# Comparator.net
KiCad netlist of a schematic drawn in Altium Designer
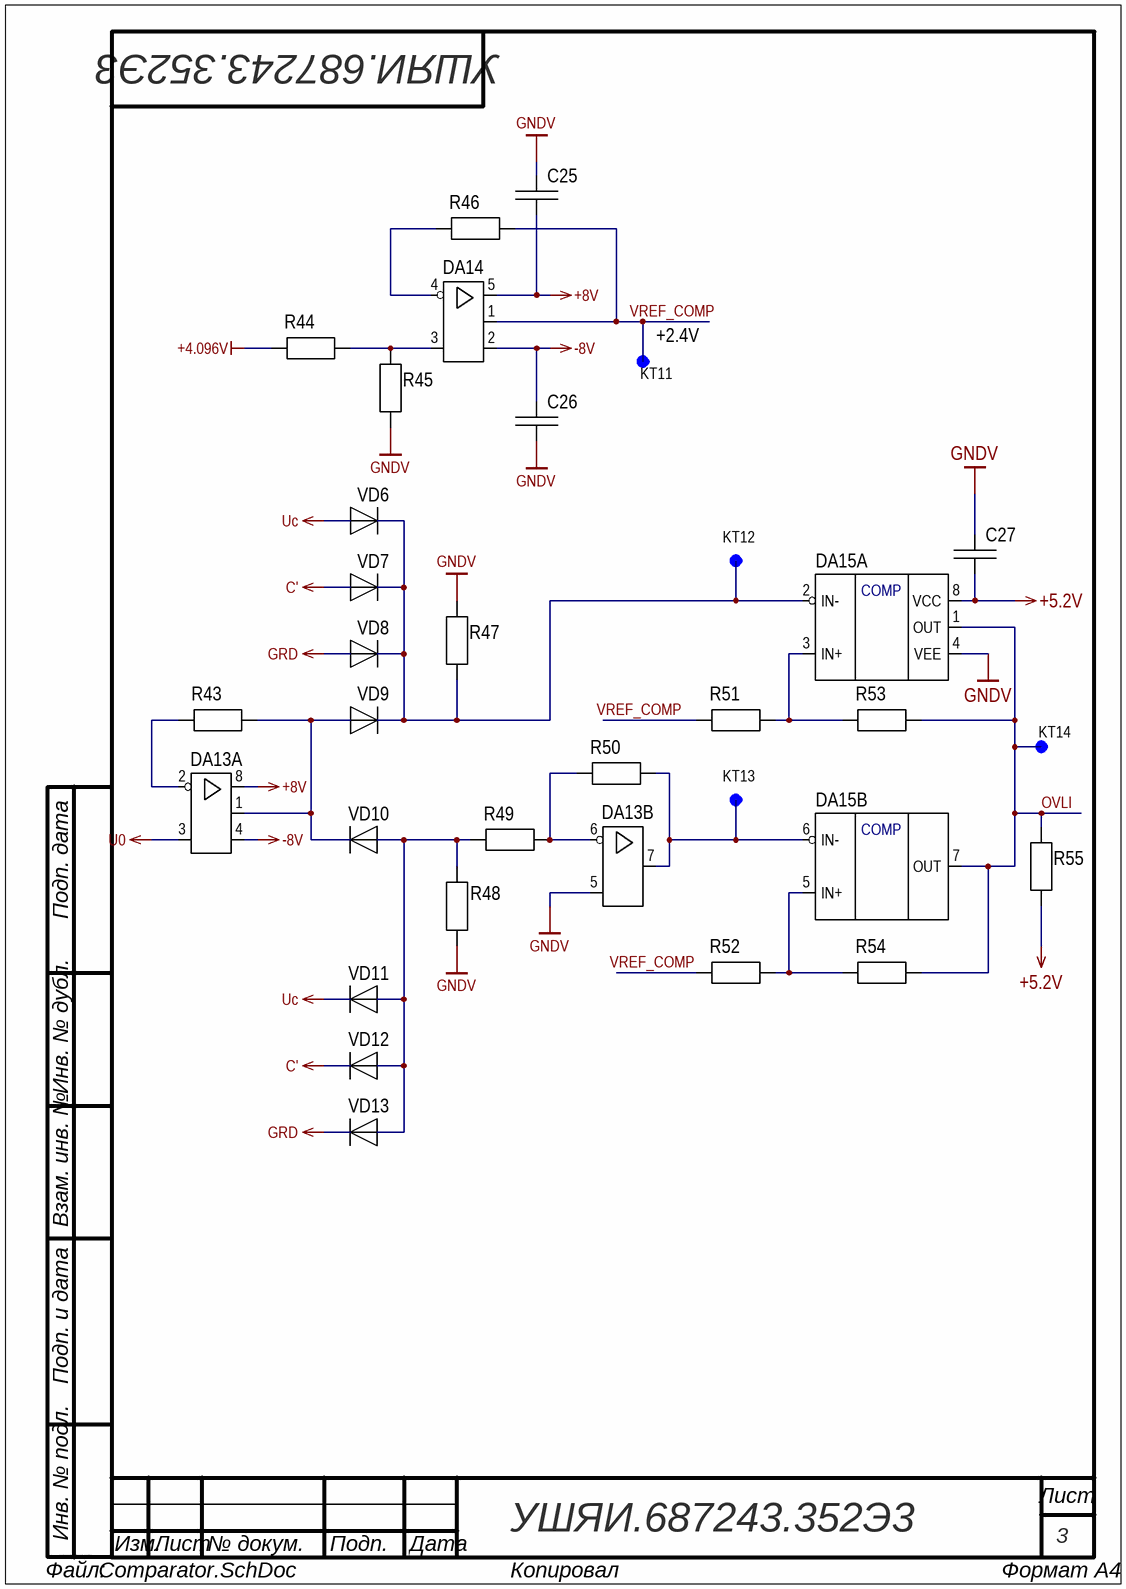
[diagram p0: Comparator.SchDoc]

(export (version "E")
  (design (tool "Eeschema 10.0.6"))
  (components
    (comp (ref "C25")
      (value "1206-X7R-50 B-0,1 мкФ+-10%")
      (footprint "standard-case:CAP: 1206")
      (libsource (lib "МНИПИ_Конденсаторы") (part "1206-X7R-50 B-0,1 мкФ+-10%"))
    )
    (comp (ref "C26")
      (value "1206-X7R-50 B-0,1 мкФ+-10%")
      (footprint "standard-case:CAP: 1206")
      (libsource (lib "МНИПИ_Конденсаторы") (part "1206-X7R-50 B-0,1 мкФ+-10%"))
    )
    (comp (ref "C27")
      (value "1206-X7R-50 B-0,1 мкФ+-10%")
      (footprint "standard-case:CAP: 1206")
      (libsource (lib "МНИПИ_Конденсаторы") (part "1206-X7R-50 B-0,1 мкФ+-10%"))
    )
    (comp (ref "DA13")
      (value "TLV9152IDR")
      (footprint "8-SOIC")
      (libsource (lib "МНИПИ_Микросхемы") (part "TLV9152IDR"))
    )
    (comp (ref "DA14")
      (value "TLV9151IDR")
      (footprint "SOT-23-5")
      (libsource (lib "МНИПИ_Микросхемы") (part "TLV9151IDR"))
    )
    (comp (ref "DA15")
      (value "TLV1842")
      (footprint "8-VSSOP")
      (description "40V, High-Speed Comparators")
      (libsource (lib "МНИПИ_Микросхемы") (part "TLV1842"))
    )
    (comp (ref "KT11") (value "OTV10") (footprint "OTV10") (libsource (lib "МНИПИ_Остальное") (part "OTV10")))
    (comp (ref "KT12") (value "OTV10") (footprint "OTV10") (libsource (lib "МНИПИ_Остальное") (part "OTV10")))
    (comp (ref "KT13") (value "OTV10") (footprint "OTV10") (libsource (lib "МНИПИ_Остальное") (part "OTV10")))
    (comp (ref "KT14") (value "OTV10") (footprint "OTV10") (libsource (lib "МНИПИ_Остальное") (part "OTV10")))
    (comp (ref "R43")
      (value "1206-470 Ом+-5%")
      (footprint "МНИПИ_Резисторы:1206")
      (libsource (lib "МНИПИ_Резисторы") (part "1206-470 Ом+-5%"))
    )
    (comp (ref "R44")
      (value "1206-7,15 кОм+-1%")
      (footprint "МНИПИ_Резисторы:1206")
      (libsource (lib "МНИПИ_Резисторы") (part "1206-7,15 кОм+-1%"))
    )
    (comp (ref "R45")
      (value "1206-10 кОм+-0,5%")
      (footprint "МНИПИ_Резисторы:1206")
      (libsource (lib "МНИПИ_Резисторы") (part "1206-10 кОм+-0,5%"))
    )
    (comp (ref "R46")
      (value "1206-470 Ом+-5%")
      (footprint "МНИПИ_Резисторы:1206")
      (libsource (lib "МНИПИ_Резисторы") (part "1206-470 Ом+-5%"))
    )
    (comp (ref "R47")
      (value "1206-2,4 кОм+-5%")
      (footprint "МНИПИ_Резисторы:1206")
      (libsource (lib "МНИПИ_Резисторы") (part "1206-2,4 кОм+-5%"))
    )
    (comp (ref "R48")
      (value "1206-2,4 кОм+-5%")
      (footprint "МНИПИ_Резисторы:1206")
      (libsource (lib "МНИПИ_Резисторы") (part "1206-2,4 кОм+-5%"))
    )
    (comp (ref "R49")
      (value "0805-1 кОм+-0,1%")
      (footprint "МНИПИ_Резисторы:0805")
      (libsource (lib "МНИПИ_Резисторы") (part "0805-1 кОм+-0,1%"))
    )
    (comp (ref "R50")
      (value "0805-1 кОм+-0,1%")
      (footprint "МНИПИ_Резисторы:0805")
      (libsource (lib "МНИПИ_Резисторы") (part "0805-1 кОм+-0,1%"))
    )
    (comp (ref "R51")
      (value "0805-1 кОм+-0,1%")
      (footprint "МНИПИ_Резисторы:0805")
      (libsource (lib "МНИПИ_Резисторы") (part "0805-1 кОм+-0,1%"))
    )
    (comp (ref "R52")
      (value "0805-1 кОм+-0,1%")
      (footprint "МНИПИ_Резисторы:0805")
      (libsource (lib "МНИПИ_Резисторы") (part "0805-1 кОм+-0,1%"))
    )
    (comp (ref "R53")
      (value "1206-510 кОм+-1%")
      (footprint "МНИПИ_Резисторы:1206")
      (libsource (lib "МНИПИ_Резисторы") (part "1206-510 кОм+-1%"))
    )
    (comp (ref "R54")
      (value "1206-510 кОм+-1%")
      (footprint "МНИПИ_Резисторы:1206")
      (libsource (lib "МНИПИ_Резисторы") (part "1206-510 кОм+-1%"))
    )
    (comp (ref "R55")
      (value "1206-4,7 кОм+-5%")
      (footprint "МНИПИ_Резисторы:1206")
      (libsource (lib "МНИПИ_Резисторы") (part "1206-4,7 кОм+-5%"))
    )
    (comp (ref "VD6")
      (value "1N4148WS")
      (footprint "SOD-323F")
      (description "Small Signal Fast Switching Diod")
      (libsource (lib "МНИПИ_Диоды") (part "1N4148WS"))
    )
    (comp (ref "VD7")
      (value "1N4148WS")
      (footprint "SOD-323F")
      (description "Small Signal Fast Switching Diod")
      (libsource (lib "МНИПИ_Диоды") (part "1N4148WS"))
    )
    (comp (ref "VD8")
      (value "1N4148WS")
      (footprint "SOD-323F")
      (description "Small Signal Fast Switching Diod")
      (libsource (lib "МНИПИ_Диоды") (part "1N4148WS"))
    )
    (comp (ref "VD9")
      (value "1N4148WS")
      (footprint "SOD-323F")
      (description "Small Signal Fast Switching Diod")
      (libsource (lib "МНИПИ_Диоды") (part "1N4148WS"))
    )
    (comp (ref "VD10")
      (value "1N4148WS")
      (footprint "SOD-323F")
      (description "Small Signal Fast Switching Diod")
      (libsource (lib "МНИПИ_Диоды") (part "1N4148WS"))
    )
    (comp (ref "VD11")
      (value "1N4148WS")
      (footprint "SOD-323F")
      (description "Small Signal Fast Switching Diod")
      (libsource (lib "МНИПИ_Диоды") (part "1N4148WS"))
    )
    (comp (ref "VD12")
      (value "1N4148WS")
      (footprint "SOD-323F")
      (description "Small Signal Fast Switching Diod")
      (libsource (lib "МНИПИ_Диоды") (part "1N4148WS"))
    )
    (comp (ref "VD13")
      (value "1N4148WS")
      (footprint "SOD-323F")
      (description "Small Signal Fast Switching Diod")
      (libsource (lib "МНИПИ_Диоды") (part "1N4148WS"))
    )
  )
  (nets
    (net (code "1") (name "+4.096V") (class "Default")
      (node (ref "R44") (pin "2") (pinfunction "2_2") (pintype "passive"))
    )
    (net (code "2") (name "+5.2V") (class "Default")
      (node (ref "C27") (pin "1") (pinfunction "1_1") (pintype "passive"))
      (node (ref "DA15") (pin "8") (pinfunction "VCC_8") (pintype "passive"))
      (node (ref "R55") (pin "1") (pinfunction "1_1") (pintype "passive"))
    )
    (net (code "3") (name "+8V") (class "Default")
      (node (ref "C25") (pin "1") (pinfunction "1_1") (pintype "passive"))
      (node (ref "DA13") (pin "8") (pinfunction "Vs+_8") (pintype "passive"))
      (node (ref "DA14") (pin "5") (pinfunction "Vs+_5") (pintype "passive"))
    )
    (net (code "4") (name "-8V") (class "Default")
      (node (ref "C26") (pin "2") (pinfunction "2_2") (pintype "passive"))
      (node (ref "DA13") (pin "4") (pinfunction "Vs-_4") (pintype "passive"))
      (node (ref "DA14") (pin "2") (pinfunction "Vs-_2") (pintype "passive"))
    )
    (net (code "5") (name "/OVLI") (class "Default")
      (node (ref "DA15") (pin "1") (pinfunction "OUT_1") (pintype "passive"))
      (node (ref "DA15") (pin "7") (pinfunction "OUT_7") (pintype "passive"))
      (node (ref "KT14") (pin "1") (pinfunction "1_1") (pintype "passive"))
      (node (ref "R53") (pin "2") (pinfunction "1_2") (pintype "passive"))
      (node (ref "R54") (pin "2") (pinfunction "1_2") (pintype "passive"))
      (node (ref "R55") (pin "2") (pinfunction "2_2") (pintype "passive"))
    )
    (net (code "6") (name "/VREF_COMP") (class "Default")
      (node (ref "DA14") (pin "1") (pinfunction "OUT_1") (pintype "passive"))
      (node (ref "KT11") (pin "1") (pinfunction "1_1") (pintype "passive"))
      (node (ref "R46") (pin "2") (pinfunction "1_2") (pintype "passive"))
      (node (ref "R51") (pin "1") (pintype "passive"))
      (node (ref "R52") (pin "2") (pintype "passive"))
    )
    (net (code "7") (name "C'") (class "Default")
      (node (ref "VD12") (pin "1") (pintype "passive"))
      (node (ref "VD7") (pin "2") (pintype "passive"))
    )
    (net (code "8") (name "GNDV") (class "Default")
      (node (ref "C25") (pin "2") (pinfunction "2_2") (pintype "passive"))
      (node (ref "C26") (pin "1") (pinfunction "1_1") (pintype "passive"))
      (node (ref "C27") (pin "2") (pinfunction "2_2") (pintype "passive"))
      (node (ref "DA13") (pin "5") (pinfunction "+IN_5") (pintype "passive"))
      (node (ref "DA15") (pin "4") (pinfunction "VEE_4") (pintype "passive"))
      (node (ref "R45") (pin "1") (pinfunction "1_1") (pintype "passive"))
      (node (ref "R47") (pin "2") (pinfunction "2_2") (pintype "passive"))
      (node (ref "R48") (pin "1") (pinfunction "1_1") (pintype "passive"))
    )
    (net (code "9") (name "GRD") (class "Default")
      (node (ref "VD13") (pin "1") (pintype "passive"))
      (node (ref "VD8") (pin "2") (pintype "passive"))
    )
    (net (code "10") (name "Net-(DA13A--IN)") (class "Default")
      (node (ref "DA13") (pin "2") (pinfunction "-IN_2") (pintype "passive"))
      (node (ref "R43") (pin "1") (pinfunction "1_1") (pintype "passive"))
    )
    (net (code "11") (name "Net-(DA13A-OUT)") (class "Default")
      (node (ref "DA13") (pin "1") (pinfunction "OUT_1") (pintype "passive"))
      (node (ref "R43") (pin "2") (pinfunction "1_2") (pintype "passive"))
      (node (ref "VD10") (pin "1") (pintype "passive"))
      (node (ref "VD9") (pin "2") (pintype "passive"))
    )
    (net (code "12") (name "Net-(DA13B--IN)") (class "Default")
      (node (ref "DA13") (pin "6") (pinfunction "-IN_6") (pintype "passive"))
      (node (ref "R49") (pin "2") (pintype "passive"))
      (node (ref "R50") (pin "1") (pintype "passive"))
    )
    (net (code "13") (name "Net-(DA13B-OUT)") (class "Default")
      (node (ref "DA13") (pin "7") (pinfunction "OUT_7") (pintype "passive"))
      (node (ref "DA15") (pin "6") (pinfunction "IN-_6") (pintype "passive"))
      (node (ref "KT13") (pin "1") (pinfunction "1_1") (pintype "passive"))
      (node (ref "R50") (pin "2") (pintype "passive"))
    )
    (net (code "14") (name "Net-(DA14-+IN)") (class "Default")
      (node (ref "DA14") (pin "3") (pinfunction "+IN_3") (pintype "passive"))
      (node (ref "R44") (pin "1") (pinfunction "1_1") (pintype "passive"))
      (node (ref "R45") (pin "2") (pinfunction "2_2") (pintype "passive"))
    )
    (net (code "15") (name "Net-(DA14--IN)") (class "Default")
      (node (ref "DA14") (pin "4") (pinfunction "-IN_4") (pintype "passive"))
      (node (ref "R46") (pin "1") (pinfunction "1_1") (pintype "passive"))
    )
    (net (code "16") (name "Net-(DA15A-IN+)") (class "Default")
      (node (ref "DA15") (pin "3") (pinfunction "IN+_3") (pintype "passive"))
      (node (ref "R51") (pin "2") (pintype "passive"))
      (node (ref "R53") (pin "1") (pinfunction "1_1") (pintype "passive"))
    )
    (net (code "17") (name "Net-(DA15A-IN-)") (class "Default")
      (node (ref "DA15") (pin "2") (pinfunction "IN-_2") (pintype "passive"))
      (node (ref "KT12") (pin "1") (pinfunction "1_1") (pintype "passive"))
      (node (ref "R47") (pin "1") (pinfunction "1_1") (pintype "passive"))
      (node (ref "VD6") (pin "1") (pintype "passive"))
      (node (ref "VD7") (pin "1") (pintype "passive"))
      (node (ref "VD8") (pin "1") (pintype "passive"))
      (node (ref "VD9") (pin "1") (pintype "passive"))
    )
    (net (code "18") (name "Net-(DA15B-IN+)") (class "Default")
      (node (ref "DA15") (pin "5") (pinfunction "IN+_5") (pintype "passive"))
      (node (ref "R52") (pin "1") (pintype "passive"))
      (node (ref "R54") (pin "1") (pinfunction "1_1") (pintype "passive"))
    )
    (net (code "19") (name "Net-(R48-Pad2)") (class "Default")
      (node (ref "R48") (pin "2") (pinfunction "2_2") (pintype "passive"))
      (node (ref "R49") (pin "1") (pintype "passive"))
      (node (ref "VD10") (pin "2") (pintype "passive"))
      (node (ref "VD11") (pin "2") (pintype "passive"))
      (node (ref "VD12") (pin "2") (pintype "passive"))
      (node (ref "VD13") (pin "2") (pintype "passive"))
    )
    (net (code "20") (name "U0") (class "Default")
      (node (ref "DA13") (pin "3") (pinfunction "+IN_3") (pintype "passive"))
    )
    (net (code "21") (name "Uc") (class "Default")
      (node (ref "VD11") (pin "1") (pintype "passive"))
      (node (ref "VD6") (pin "2") (pintype "passive"))
    )
  )
)
